# Mezz_connector.net
KiCad netlist of a schematic drawn in Altium Designer
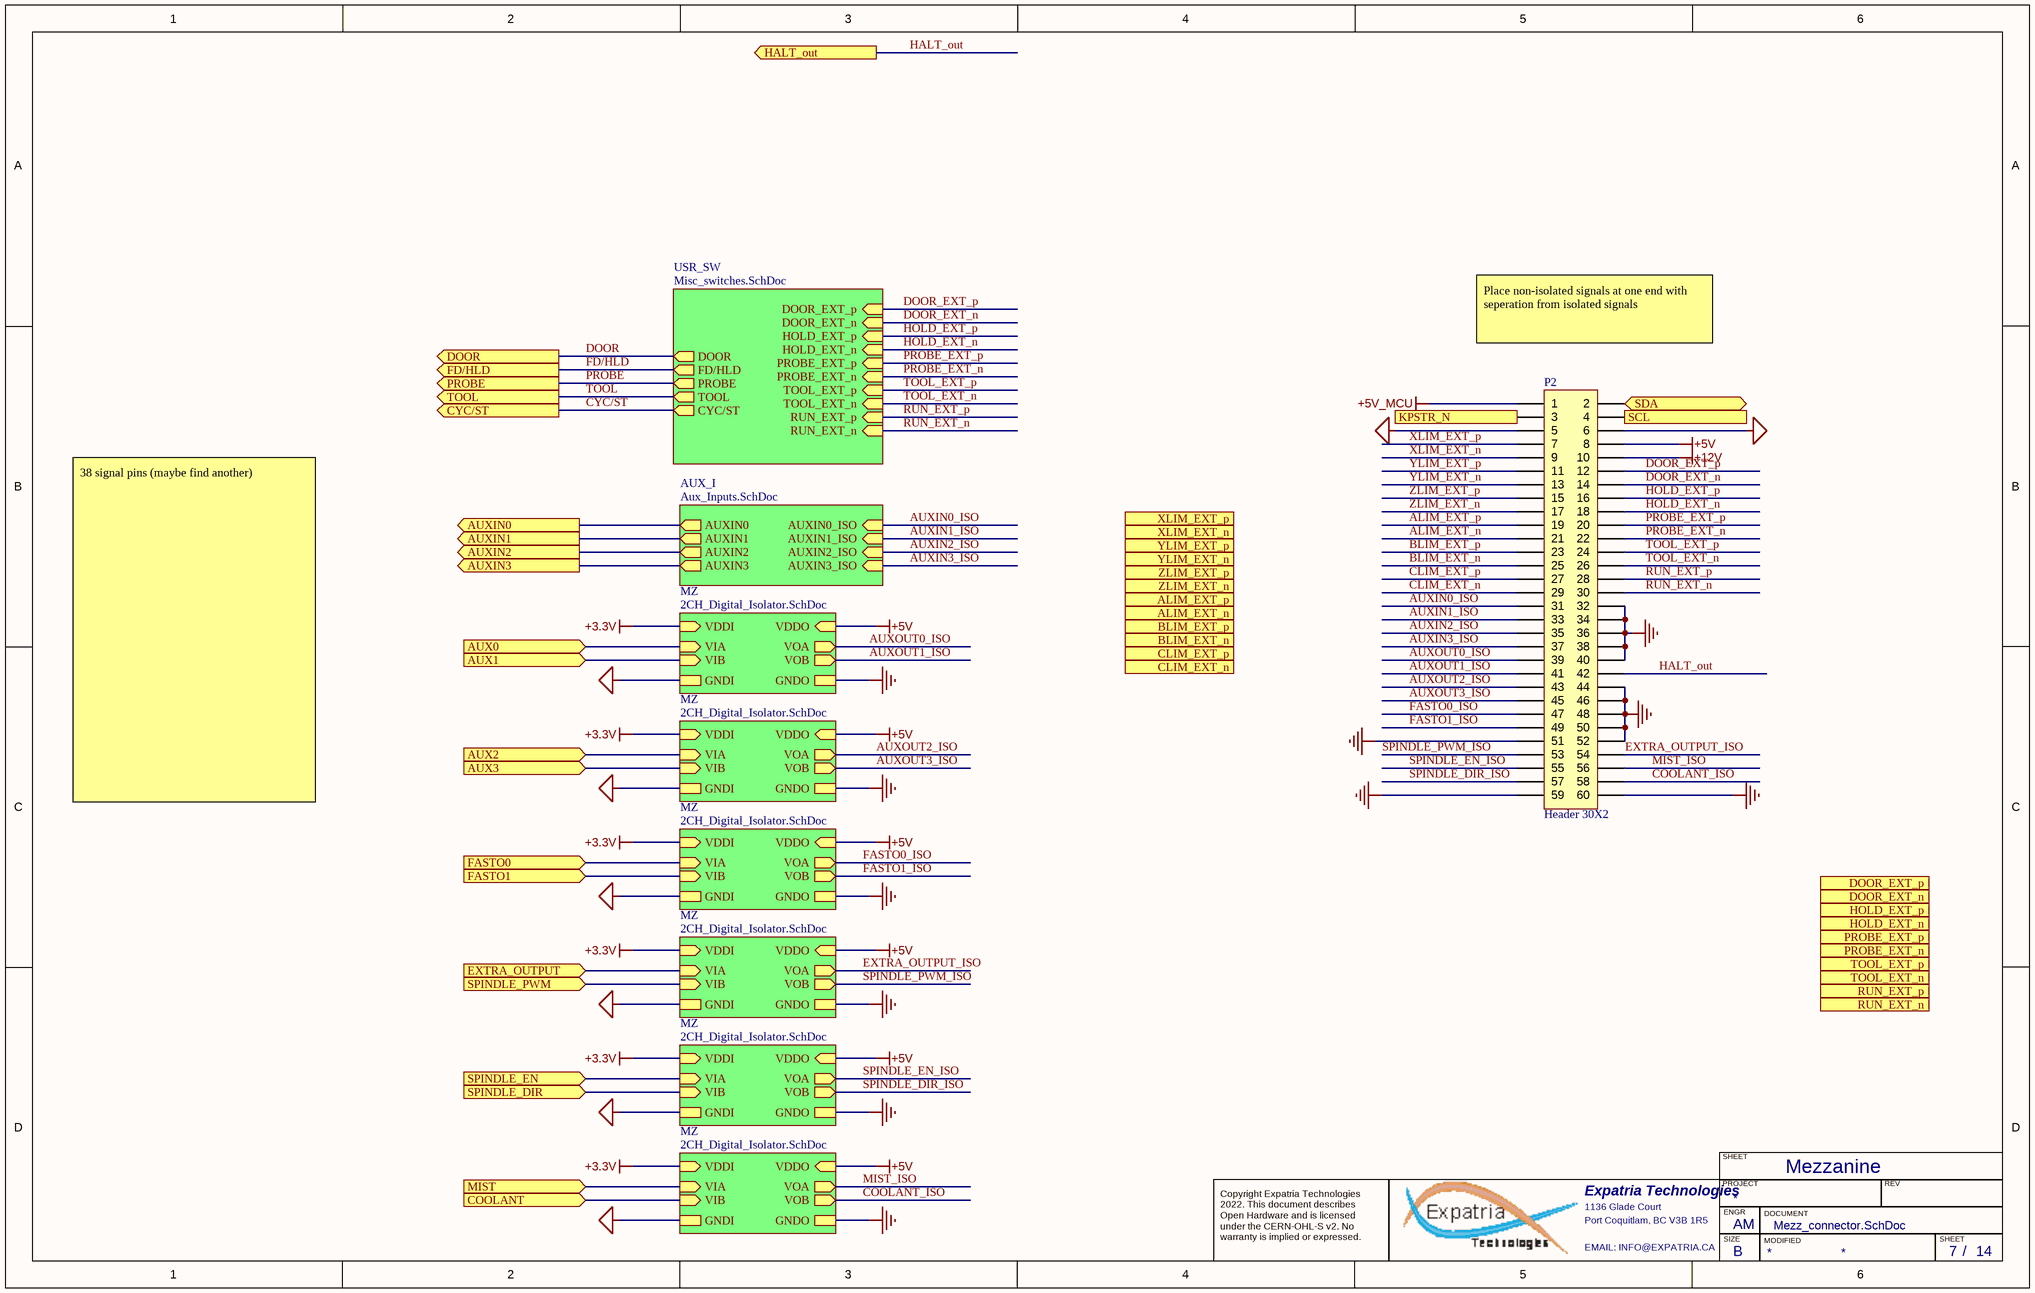
[diagram p0: Mezz_connector.SchDoc]

(export (version "E")
  (design (tool "Eeschema 10.0.6"))
  (components
    (comp (ref "P2")
      (value "Header 30X2")
      (footprint "HDR2X30")
      (description "Header, 30-Pin, Dual row")
      (fields (field (name "PUBLISHER") "Altium Limited"))
      (libsource (lib "Miscellaneous Connectors") (part "Header 30X2"))
    )
  )
  (nets
    (net (code "2") (name "+5V") (class "Default")
      (node (ref "P2") (pin "8") (pinfunction "8_8") (pintype "passive"))
    )
    (net (code "3") (name "+5V_MCU") (class "Default")
      (node (ref "P2") (pin "1") (pinfunction "1_1") (pintype "passive"))
    )
    (net (code "4") (name "+12V") (class "Default")
      (node (ref "P2") (pin "10") (pinfunction "10_10") (pintype "passive"))
    )
    (net (code "5") (name "/ALIM_EXT_n") (class "Default")
      (node (ref "P2") (pin "21") (pinfunction "21_21") (pintype "passive"))
    )
    (net (code "6") (name "/ALIM_EXT_p") (class "Default")
      (node (ref "P2") (pin "19") (pinfunction "19_19") (pintype "passive"))
    )
    (net (code "12") (name "/AUXIN0_ISO") (class "Default")
      (node (ref "P2") (pin "31") (pinfunction "31_31") (pintype "passive"))
    )
    (net (code "14") (name "/AUXIN1_ISO") (class "Default")
      (node (ref "P2") (pin "33") (pinfunction "33_33") (pintype "passive"))
    )
    (net (code "16") (name "/AUXIN2_ISO") (class "Default")
      (node (ref "P2") (pin "35") (pinfunction "35_35") (pintype "passive"))
    )
    (net (code "18") (name "/AUXIN3_ISO") (class "Default")
      (node (ref "P2") (pin "37") (pinfunction "37_37") (pintype "passive"))
    )
    (net (code "19") (name "/AUXOUT0_ISO") (class "Default")
      (node (ref "P2") (pin "39") (pinfunction "39_39") (pintype "passive"))
    )
    (net (code "20") (name "/AUXOUT1_ISO") (class "Default")
      (node (ref "P2") (pin "41") (pinfunction "41_41") (pintype "passive"))
    )
    (net (code "21") (name "/AUXOUT2_ISO") (class "Default")
      (node (ref "P2") (pin "43") (pinfunction "43_43") (pintype "passive"))
    )
    (net (code "22") (name "/AUXOUT3_ISO") (class "Default")
      (node (ref "P2") (pin "45") (pinfunction "45_45") (pintype "passive"))
    )
    (net (code "23") (name "/BLIM_EXT_n") (class "Default")
      (node (ref "P2") (pin "25") (pinfunction "25_25") (pintype "passive"))
    )
    (net (code "24") (name "/BLIM_EXT_p") (class "Default")
      (node (ref "P2") (pin "23") (pinfunction "23_23") (pintype "passive"))
    )
    (net (code "25") (name "/CLIM_EXT_n") (class "Default")
      (node (ref "P2") (pin "29") (pinfunction "29_29") (pintype "passive"))
    )
    (net (code "26") (name "/CLIM_EXT_p") (class "Default")
      (node (ref "P2") (pin "27") (pinfunction "27_27") (pintype "passive"))
    )
    (net (code "28") (name "/COOLANT_ISO") (class "Default")
      (node (ref "P2") (pin "58") (pinfunction "58_58") (pintype "passive"))
    )
    (net (code "31") (name "/DOOR_EXT_n") (class "Default")
      (node (ref "P2") (pin "14") (pinfunction "14_14") (pintype "passive"))
    )
    (net (code "32") (name "/DOOR_EXT_p") (class "Default")
      (node (ref "P2") (pin "12") (pinfunction "12_12") (pintype "passive"))
    )
    (net (code "34") (name "/EXTRA_OUTPUT_ISO") (class "Default")
      (node (ref "P2") (pin "54") (pinfunction "54_54") (pintype "passive"))
    )
    (net (code "36") (name "/FASTO0_ISO") (class "Default")
      (node (ref "P2") (pin "47") (pinfunction "47_47") (pintype "passive"))
    )
    (net (code "38") (name "/FASTO1_ISO") (class "Default")
      (node (ref "P2") (pin "49") (pinfunction "49_49") (pintype "passive"))
    )
    (net (code "40") (name "/HALT_out") (class "Default")
      (node (ref "P2") (pin "42") (pinfunction "42_42") (pintype "passive"))
    )
    (net (code "41") (name "/HOLD_EXT_n") (class "Default")
      (node (ref "P2") (pin "18") (pinfunction "18_18") (pintype "passive"))
    )
    (net (code "42") (name "/HOLD_EXT_p") (class "Default")
      (node (ref "P2") (pin "16") (pinfunction "16_16") (pintype "passive"))
    )
    (net (code "43") (name "/KPSTR_N") (class "Default")
      (node (ref "P2") (pin "3") (pinfunction "3_3") (pintype "passive"))
    )
    (net (code "45") (name "/MIST_ISO") (class "Default")
      (node (ref "P2") (pin "56") (pinfunction "56_56") (pintype "passive"))
    )
    (net (code "47") (name "/PROBE_EXT_n") (class "Default")
      (node (ref "P2") (pin "22") (pinfunction "22_22") (pintype "passive"))
    )
    (net (code "48") (name "/PROBE_EXT_p") (class "Default")
      (node (ref "P2") (pin "20") (pinfunction "20_20") (pintype "passive"))
    )
    (net (code "49") (name "/RUN_EXT_n") (class "Default")
      (node (ref "P2") (pin "30") (pinfunction "30_30") (pintype "passive"))
    )
    (net (code "50") (name "/RUN_EXT_p") (class "Default")
      (node (ref "P2") (pin "28") (pinfunction "28_28") (pintype "passive"))
    )
    (net (code "51") (name "/SCL") (class "Default")
      (node (ref "P2") (pin "4") (pinfunction "4_4") (pintype "passive"))
    )
    (net (code "52") (name "/SDA") (class "Default")
      (node (ref "P2") (pin "2") (pinfunction "2_2") (pintype "passive"))
    )
    (net (code "54") (name "/SPINDLE_DIR_ISO") (class "Default")
      (node (ref "P2") (pin "57") (pinfunction "57_57") (pintype "passive"))
    )
    (net (code "56") (name "/SPINDLE_EN_ISO") (class "Default")
      (node (ref "P2") (pin "55") (pinfunction "55_55") (pintype "passive"))
    )
    (net (code "58") (name "/SPINDLE_PWM_ISO") (class "Default")
      (node (ref "P2") (pin "53") (pinfunction "53_53") (pintype "passive"))
    )
    (net (code "60") (name "/TOOL_EXT_n") (class "Default")
      (node (ref "P2") (pin "26") (pinfunction "26_26") (pintype "passive"))
    )
    (net (code "61") (name "/TOOL_EXT_p") (class "Default")
      (node (ref "P2") (pin "24") (pinfunction "24_24") (pintype "passive"))
    )
    (net (code "62") (name "/XLIM_EXT_n") (class "Default")
      (node (ref "P2") (pin "9") (pinfunction "9_9") (pintype "passive"))
    )
    (net (code "63") (name "/XLIM_EXT_p") (class "Default")
      (node (ref "P2") (pin "7") (pinfunction "7_7") (pintype "passive"))
    )
    (net (code "64") (name "/YLIM_EXT_n") (class "Default")
      (node (ref "P2") (pin "13") (pinfunction "13_13") (pintype "passive"))
    )
    (net (code "65") (name "/YLIM_EXT_p") (class "Default")
      (node (ref "P2") (pin "11") (pinfunction "11_11") (pintype "passive"))
    )
    (net (code "66") (name "/ZLIM_EXT_n") (class "Default")
      (node (ref "P2") (pin "17") (pinfunction "17_17") (pintype "passive"))
    )
    (net (code "67") (name "/ZLIM_EXT_p") (class "Default")
      (node (ref "P2") (pin "15") (pinfunction "15_15") (pintype "passive"))
    )
    (net (code "68") (name "GND") (class "Default")
      (node (ref "P2") (pin "32") (pinfunction "32_32") (pintype "passive"))
      (node (ref "P2") (pin "34") (pinfunction "34_34") (pintype "passive"))
      (node (ref "P2") (pin "36") (pinfunction "36_36") (pintype "passive"))
      (node (ref "P2") (pin "38") (pinfunction "38_38") (pintype "passive"))
      (node (ref "P2") (pin "40") (pinfunction "40_40") (pintype "passive"))
      (node (ref "P2") (pin "44") (pinfunction "44_44") (pintype "passive"))
      (node (ref "P2") (pin "46") (pinfunction "46_46") (pintype "passive"))
      (node (ref "P2") (pin "48") (pinfunction "48_48") (pintype "passive"))
      (node (ref "P2") (pin "50") (pinfunction "50_50") (pintype "passive"))
      (node (ref "P2") (pin "51") (pinfunction "51_51") (pintype "passive"))
      (node (ref "P2") (pin "52") (pinfunction "52_52") (pintype "passive"))
      (node (ref "P2") (pin "59") (pinfunction "59_59") (pintype "passive"))
      (node (ref "P2") (pin "60") (pinfunction "60_60") (pintype "passive"))
    )
    (net (code "69") (name "MCU_GND") (class "Default")
      (node (ref "P2") (pin "5") (pinfunction "5_5") (pintype "passive"))
      (node (ref "P2") (pin "6") (pinfunction "6_6") (pintype "passive"))
    )
  )
)
